# 411618_029_3_4.net
KiCad netlist of a schematic drawn in Altium Designer
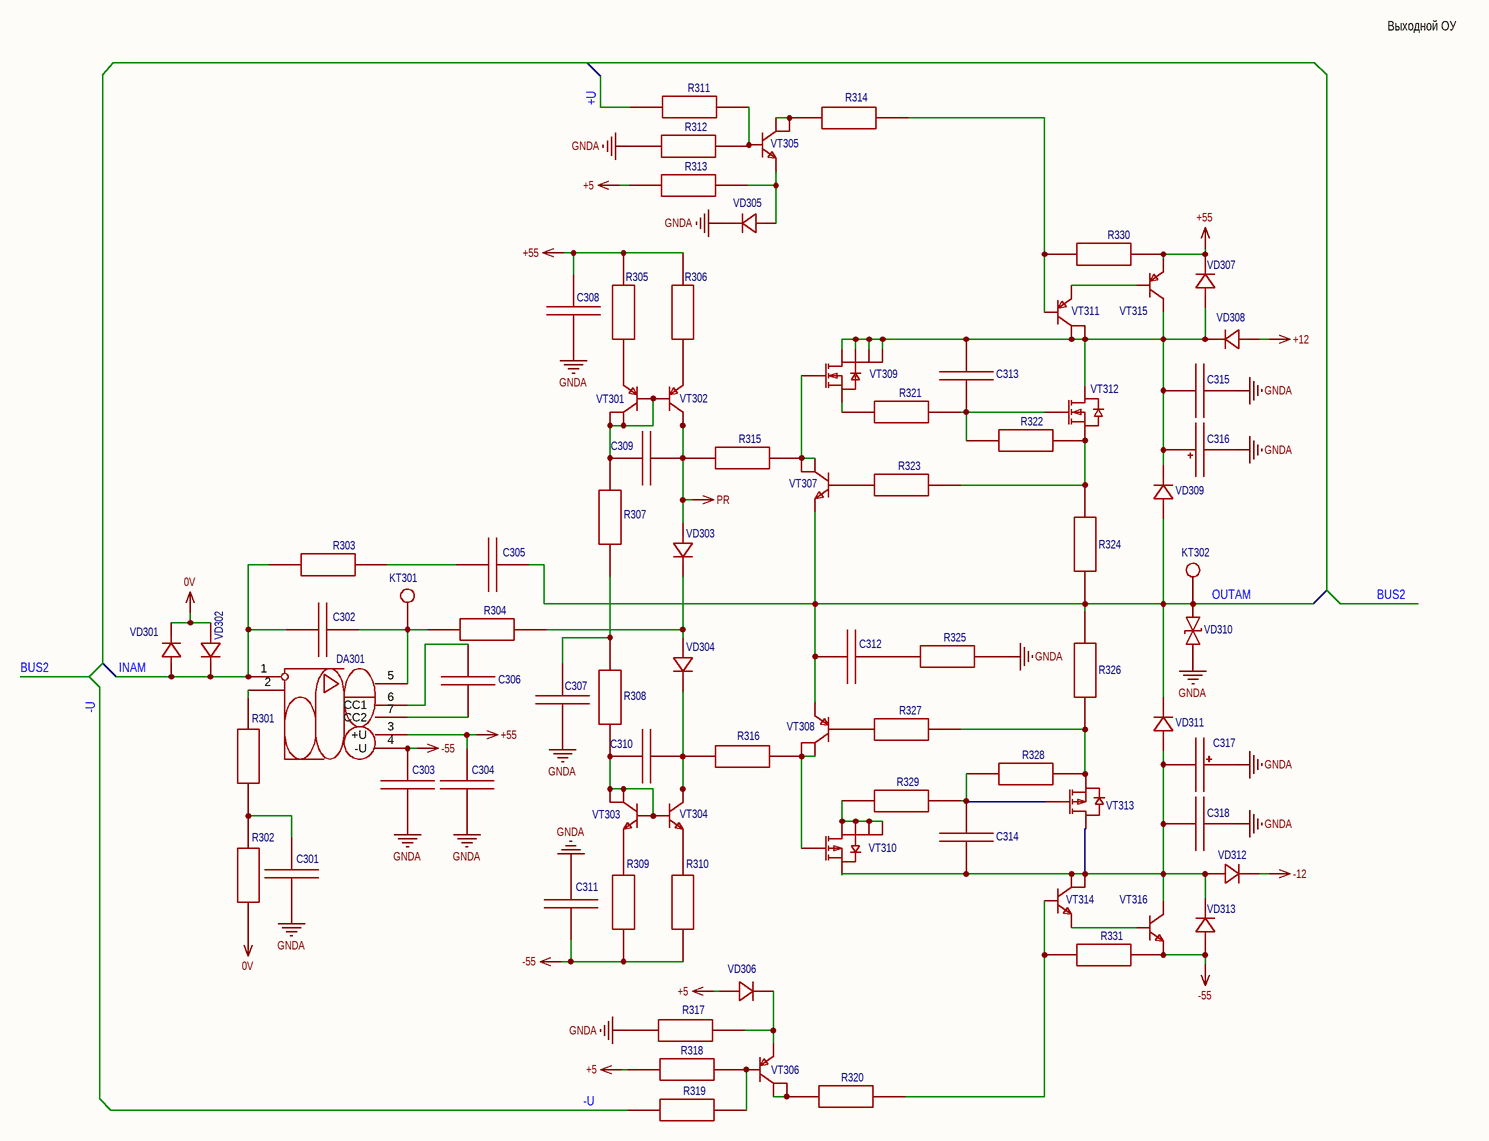
[diagram p0: УШЯИ.411618.029Э Э3 Лист 4.schdoc]

(export (version "E")
  (design (tool "Eeschema 10.0.6"))
  (components
    (comp (ref "C301")
      (value "Конденсатор SMD 1мкФ 100В X7R 10% [0805]")
      (footprint "C0805")
      (fields (field (name "MANUFACTURER PART") "C0805") (field (name "CONTRIBUTOR") "jordanjin"))
      (libsource (lib "altium-import") (part "root_1_Конденсатор SMD 1мкФ 100В X7R 10% [0805]_"))
    )
    (comp (ref "C302")
      (value "Конденсатор SMD 33пФ 100В X7R 10% [0805]")
      (footprint "C0805")
      (fields (field (name "MANUFACTURER PART") "C0805") (field (name "CONTRIBUTOR") "jordanjin"))
      (libsource (lib "altium-import") (part "root_2_Конденсатор SMD 33пФ 100В X7R 10% [0805]_"))
    )
    (comp (ref "C303")
      (value "Конденсатор SMD 68нФ 100В X7R 10% [0805]")
      (footprint "C0805")
      (fields (field (name "MANUFACTURER PART") "C0805") (field (name "CONTRIBUTOR") "jordanjin"))
      (libsource (lib "altium-import") (part "root_1_Конденсатор SMD 68нФ 100В X7R 10% [0805]_"))
    )
    (comp (ref "C304")
      (value "Конденсатор SMD 68нФ 100В X7R 10% [0805]")
      (footprint "C0805")
      (fields (field (name "MANUFACTURER PART") "C0805") (field (name "CONTRIBUTOR") "jordanjin"))
      (libsource (lib "altium-import") (part "root_1_Конденсатор SMD 68нФ 100В X7R 10% [0805]_"))
    )
    (comp (ref "C305")
      (value "Конденсатор SMD 10пФ 100В X7R 10% [0805]")
      (footprint "C0805")
      (fields (field (name "MANUFACTURER PART") "C0805") (field (name "CONTRIBUTOR") "jordanjin"))
      (libsource (lib "altium-import") (part "root_2_Конденсатор SMD 10пФ 100В X7R 10% [0805]_"))
    )
    (comp (ref "C306")
      (value "Конденсатор SMD 10пФ 100В X7R 10% [0805]")
      (footprint "C0805")
      (fields (field (name "MANUFACTURER PART") "C0805") (field (name "CONTRIBUTOR") "jordanjin"))
      (libsource (lib "altium-import") (part "root_3_Конденсатор SMD 10пФ 100В X7R 10% [0805]_"))
    )
    (comp (ref "C307")
      (value "Конденсатор SMD 68нФ 250В X7R 10% [0805]")
      (footprint "C0805")
      (fields (field (name "MANUFACTURER PART") "C0805") (field (name "CONTRIBUTOR") "jordanjin"))
      (libsource (lib "altium-import") (part "root_1_Конденсатор SMD 68нФ 250В X7R 10% [0805]_"))
    )
    (comp (ref "C308")
      (value "Конденсатор SMD 68нФ 250В X7R 10% [0805]")
      (footprint "C0805")
      (fields (field (name "MANUFACTURER PART") "C0805") (field (name "CONTRIBUTOR") "jordanjin"))
      (libsource (lib "altium-import") (part "root_3_Конденсатор SMD 68нФ 250В X7R 10% [0805]_"))
    )
    (comp (ref "C309")
      (value "Конденсатор SMD 10пФ 100В X7R 10% [0805]")
      (footprint "C0805")
      (fields (field (name "MANUFACTURER PART") "C0805") (field (name "CONTRIBUTOR") "jordanjin"))
      (libsource (lib "altium-import") (part "root_2_Конденсатор SMD 10пФ 100В X7R 10% [0805]_"))
    )
    (comp (ref "C310")
      (value "Конденсатор SMD 10пФ 100В X7R 10% [0805]")
      (footprint "C0805")
      (fields (field (name "MANUFACTURER PART") "C0805") (field (name "CONTRIBUTOR") "jordanjin"))
      (libsource (lib "") (part "root_2_Конденсатор SMD 10пФ 100В X7R 10% [0805]__1"))
    )
    (comp (ref "C311")
      (value "Конденсатор SMD 68нФ 250В X7R 10% [0805]")
      (footprint "C0805")
      (fields (field (name "MANUFACTURER PART") "C0805") (field (name "CONTRIBUTOR") "jordanjin"))
      (libsource (lib "altium-import") (part "root_3_Конденсатор SMD 68нФ 250В X7R 10% [0805]_"))
    )
    (comp (ref "C312")
      (value "Конденсатор SMD 10пФ 100В X7R 10% [0805]")
      (footprint "C0805")
      (fields (field (name "MANUFACTURER PART") "C0805") (field (name "CONTRIBUTOR") "jordanjin"))
      (libsource (lib "altium-import") (part "root_0_Конденсатор SMD 10пФ 100В X7R 10% [0805]_"))
    )
    (comp (ref "C313")
      (value "Конденсатор SMD 10пФ 100В X7R 10% [0805]")
      (footprint "C0805")
      (fields (field (name "MANUFACTURER PART") "C0805") (field (name "CONTRIBUTOR") "jordanjin"))
      (libsource (lib "altium-import") (part "root_3_Конденсатор SMD 10пФ 100В X7R 10% [0805]_"))
    )
    (comp (ref "C314")
      (value "Конденсатор SMD 10пФ 100В X7R 10% [0805]")
      (footprint "C0805")
      (fields (field (name "MANUFACTURER PART") "C0805") (field (name "CONTRIBUTOR") "jordanjin"))
      (libsource (lib "altium-import") (part "root_3_Конденсатор SMD 10пФ 100В X7R 10% [0805]_"))
    )
    (comp (ref "C315")
      (value "Конденсатор SMD 10пФ 100В X7R 10% [0805]")
      (footprint "C0805")
      (fields (field (name "MANUFACTURER PART") "C0805") (field (name "CONTRIBUTOR") "jordanjin"))
      (libsource (lib "altium-import") (part "root_0_Конденсатор SMD 10пФ 100В X7R 10% [0805]_"))
    )
    (comp (ref "C316")
      (value "ECAP (К50-35), 220мкФ, 100В, 105°C, 13x25, p:5мм")
      (footprint "CAP-TH_BD13.0-P5.00-D0.6-FD")
      (fields
        (field (name "MANUFACTURER") "JB Capacitors")
        (field (name "MANUFACTURER PART") "JRB2A221M05001300250000B")
        (field (name "CONTRIBUTOR") "jordanjin")
      )
      (libsource (lib "altium-import") (part "root_1_ECAP (К50-35), 220мкФ, 100В, 105°C, 13x25, p{colon}5мм_"))
    )
    (comp (ref "C317")
      (value "ECAP (К50-35), 220мкФ, 100В, 105°C, 13x25, p:5мм")
      (footprint "CAP-TH_BD13.0-P5.00-D0.6-FD")
      (fields
        (field (name "MANUFACTURER") "JB Capacitors")
        (field (name "MANUFACTURER PART") "JRB2A221M05001300250000B")
        (field (name "CONTRIBUTOR") "jordanjin")
      )
      (libsource (lib "altium-import") (part "root_3_ECAP (К50-35), 220мкФ, 100В, 105°C, 13x25, p{colon}5мм_"))
    )
    (comp (ref "C318")
      (value "Конденсатор SMD 10пФ 100В X7R 10% [0805]")
      (footprint "C0805")
      (fields (field (name "MANUFACTURER PART") "C0805") (field (name "CONTRIBUTOR") "jordanjin"))
      (libsource (lib "altium-import") (part "root_0_Конденсатор SMD 10пФ 100В X7R 10% [0805]_"))
    )
    (comp (ref "DA301")
      (value "Операционный усилитель PA340CC [TH]")
      (fields
        (field (name "MANUFACTURER") "Apex Microtechnology")
        (field (name "MANUFACTURER PART") "PA340CC")
        (field (name "CONTRIBUTOR") "jordanjin")
      )
      (libsource (lib "altium-import") (part "root_0_Операционный усилитель PA340CC [TH]_"))
    )
    (comp (ref "KT301")
      (value "Control point")
      (fields (field (name "CONTRIBUTOR") "jordanjin"))
      (libsource (lib "altium-import") (part "root_2_Control point_"))
    )
    (comp (ref "KT302")
      (value "Control point")
      (fields (field (name "CONTRIBUTOR") "jordanjin"))
      (libsource (lib "altium-import") (part "root_2_Control point_"))
    )
    (comp (ref "R301")
      (value "Резистор 4.6кОм 0,125Вт 1% [0805]")
      (footprint "R0805")
      (fields (field (name "MANUFACTURER PART") "R0805") (field (name "CONTRIBUTOR") "jordanjin"))
      (libsource (lib "altium-import") (part "root_1_Резистор 4.6кОм 0,125Вт 1% [0805]_"))
    )
    (comp (ref "R302")
      (value "Резистор 1.2кОм 0,125Вт 1% [0805]")
      (footprint "R0805")
      (fields (field (name "MANUFACTURER PART") "R0805") (field (name "CONTRIBUTOR") "jordanjin"))
      (libsource (lib "altium-import") (part "root_1_Резистор 1.2кОм 0,125Вт 1% [0805]_"))
    )
    (comp (ref "R303")
      (value "Резистор 1.8кОм 0,125Вт 1% [0805]")
      (footprint "R0805")
      (fields (field (name "MANUFACTURER PART") "R0805") (field (name "CONTRIBUTOR") "jordanjin"))
      (libsource (lib "altium-import") (part "root_2_Резистор 1.8кОм 0,125Вт 1% [0805]_"))
    )
    (comp (ref "R304")
      (value "Резистор 1.2кОм 0,125Вт 1% [0805]")
      (footprint "R0805")
      (fields (field (name "MANUFACTURER PART") "R0805") (field (name "CONTRIBUTOR") "jordanjin"))
      (libsource (lib "altium-import") (part "root_2_Резистор 1.2кОм 0,125Вт 1% [0805]_"))
    )
    (comp (ref "R305")
      (value "Резистор 220Ом 0,125Вт 1% [0805]")
      (footprint "R0805")
      (fields (field (name "MANUFACTURER PART") "R0805") (field (name "CONTRIBUTOR") "jordanjin"))
      (libsource (lib "") (part "root_3_Резистор 220Ом 0,125Вт 1% [0805]__1"))
    )
    (comp (ref "R306")
      (value "Резистор 220Ом 0,125Вт 1% [0805]")
      (footprint "R0805")
      (fields (field (name "MANUFACTURER PART") "R0805") (field (name "CONTRIBUTOR") "jordanjin"))
      (libsource (lib "") (part "root_3_Резистор 220Ом 0,125Вт 1% [0805]__1"))
    )
    (comp (ref "R307")
      (value "Резистор 22кОм 0,125Вт 1% [0805]")
      (footprint "R0805")
      (fields (field (name "MANUFACTURER PART") "R0805") (field (name "CONTRIBUTOR") "jordanjin"))
      (libsource (lib "altium-import") (part "root_3_Резистор 22кОм 0,125Вт 1% [0805]_"))
    )
    (comp (ref "R308")
      (value "Резистор 22кОм 0,125Вт 1% [0805]")
      (footprint "R0805")
      (fields (field (name "MANUFACTURER PART") "R0805") (field (name "CONTRIBUTOR") "jordanjin"))
      (libsource (lib "") (part "root_3_Резистор 22кОм 0,125Вт 1% [0805]__1"))
    )
    (comp (ref "R309")
      (value "Резистор 220Ом 0,125Вт 1% [0805]")
      (footprint "R0805")
      (fields (field (name "MANUFACTURER PART") "R0805") (field (name "CONTRIBUTOR") "jordanjin"))
      (libsource (lib "altium-import") (part "root_3_Резистор 220Ом 0,125Вт 1% [0805]_"))
    )
    (comp (ref "R310")
      (value "Резистор 220Ом 0,125Вт 1% [0805]")
      (footprint "R0805")
      (fields (field (name "MANUFACTURER PART") "R0805") (field (name "CONTRIBUTOR") "jordanjin"))
      (libsource (lib "altium-import") (part "root_3_Резистор 220Ом 0,125Вт 1% [0805]_"))
    )
    (comp (ref "R311")
      (value "Резистор 3кОм 0,125Вт 1% [0805]")
      (footprint "R0805")
      (fields (field (name "MANUFACTURER PART") "R0805") (field (name "CONTRIBUTOR") "jordanjin"))
      (libsource (lib "") (part "root_0_Резистор 3кОм 0,125Вт 1% [0805]__1"))
    )
    (comp (ref "R312")
      (value "Резистор 2.4кОм 0,125Вт 1% [0805]")
      (footprint "R0805")
      (fields (field (name "MANUFACTURER PART") "R0805") (field (name "CONTRIBUTOR") "jordanjin"))
      (libsource (lib "") (part "root_0_Резистор 2.4кОм 0,125Вт 1% [0805]__1"))
    )
    (comp (ref "R313")
      (value "Резистор 7.2кОм 0,125Вт 1% [0805]")
      (footprint "R0805")
      (fields (field (name "MANUFACTURER PART") "R0805") (field (name "CONTRIBUTOR") "jordanjin"))
      (libsource (lib "") (part "root_0_Резистор 7.2кОм 0,125Вт 1% [0805]__1"))
    )
    (comp (ref "R314")
      (value "Резистор 18кОм 0,125Вт 1% [0805]")
      (footprint "R0805")
      (fields (field (name "MANUFACTURER PART") "R0805") (field (name "CONTRIBUTOR") "jordanjin"))
      (libsource (lib "altium-import") (part "root_0_Резистор 18кОм 0,125Вт 1% [0805]_"))
    )
    (comp (ref "R315")
      (value "Резистор 120Ом 0,125Вт 1% [0805]")
      (footprint "R0805")
      (fields (field (name "MANUFACTURER PART") "R0805") (field (name "CONTRIBUTOR") "jordanjin"))
      (libsource (lib "altium-import") (part "root_0_Резистор 120Ом 0,125Вт 1% [0805]_"))
    )
    (comp (ref "R316")
      (value "Резистор 120Ом 0,125Вт 1% [0805]")
      (footprint "R0805")
      (fields (field (name "MANUFACTURER PART") "R0805") (field (name "CONTRIBUTOR") "jordanjin"))
      (libsource (lib "altium-import") (part "root_0_Резистор 120Ом 0,125Вт 1% [0805]_"))
    )
    (comp (ref "R317")
      (value "Резистор 7.2кОм 0,125Вт 1% [0805]")
      (footprint "R0805")
      (fields (field (name "MANUFACTURER PART") "R0805") (field (name "CONTRIBUTOR") "jordanjin"))
      (libsource (lib "altium-import") (part "root_0_Резистор 7.2кОм 0,125Вт 1% [0805]_"))
    )
    (comp (ref "R318")
      (value "Резистор 2.4кОм 0,125Вт 1% [0805]")
      (footprint "R0805")
      (fields (field (name "MANUFACTURER PART") "R0805") (field (name "CONTRIBUTOR") "jordanjin"))
      (libsource (lib "altium-import") (part "root_0_Резистор 2.4кОм 0,125Вт 1% [0805]_"))
    )
    (comp (ref "R319")
      (value "Резистор 3кОм 0,125Вт 1% [0805]")
      (footprint "R0805")
      (fields (field (name "MANUFACTURER PART") "R0805") (field (name "CONTRIBUTOR") "jordanjin"))
      (libsource (lib "altium-import") (part "root_0_Резистор 3кОм 0,125Вт 1% [0805]_"))
    )
    (comp (ref "R320")
      (value "Резистор 18кОм 0,125Вт 1% [0805]")
      (footprint "R0805")
      (fields (field (name "MANUFACTURER PART") "R0805") (field (name "CONTRIBUTOR") "jordanjin"))
      (libsource (lib "") (part "root_0_Резистор 18кОм 0,125Вт 1% [0805]__1"))
    )
    (comp (ref "R321")
      (value "Резистор 240Ом 0.25Вт 1% [1206]")
      (footprint "R0805")
      (fields (field (name "MANUFACTURER PART") "R0805") (field (name "CONTRIBUTOR") "jordanjin"))
      (libsource (lib "") (part "root_0_Резистор 240Ом 0.25Вт 1% [1206]__1"))
    )
    (comp (ref "R322")
      (value "Резистор 1кОм 0,125Вт 5% [0805]")
      (footprint "R0805")
      (fields (field (name "MANUFACTURER PART") "R0805") (field (name "CONTRIBUTOR") "jordanjin"))
      (libsource (lib "altium-import") (part "root_2_Резистор 1кОм 0,125Вт 5% [0805]_"))
    )
    (comp (ref "R323")
      (value "Резистор 300Ом 0,125Вт 1% [0805]")
      (footprint "R0805")
      (fields (field (name "MANUFACTURER PART") "R0805") (field (name "CONTRIBUTOR") "jordanjin"))
      (libsource (lib "") (part "root_0_Резистор 300Ом 0,125Вт 1% [0805]__1"))
    )
    (comp (ref "R324")
      (value "Резистор MP930-0.04-1% [TO-220-2]")
      (footprint "TO-220-2_L10.4-W3.2-P5.08-L")
      (fields (field (name "MANUFACTURER PART") "MP930-0.04-1%") (field (name "CONTRIBUTOR") "jordanjin"))
      (libsource (lib "altium-import") (part "root_1_Резистор MP930-0.04-1% [TO-220-2]_"))
    )
    (comp (ref "R325")
      (value "Резистор 100Ом 0,125Вт 1% [0805]")
      (footprint "R0805")
      (fields (field (name "MANUFACTURER PART") "R0805") (field (name "CONTRIBUTOR") "jordanjin"))
      (libsource (lib "altium-import") (part "root_0_Резистор 100Ом 0,125Вт 1% [0805]_"))
    )
    (comp (ref "R326")
      (value "Резистор MP930-0.04-1% [TO-220-2]")
      (footprint "TO-220-2_L10.4-W3.2-P5.08-L")
      (fields (field (name "MANUFACTURER PART") "MP930-0.04-1%") (field (name "CONTRIBUTOR") "jordanjin"))
      (libsource (lib "") (part "root_1_Резистор MP930-0.04-1% [TO-220-2]__1"))
    )
    (comp (ref "R327")
      (value "Резистор 300Ом 0,125Вт 1% [0805]")
      (footprint "R0805")
      (fields (field (name "MANUFACTURER PART") "R0805") (field (name "CONTRIBUTOR") "jordanjin"))
      (libsource (lib "altium-import") (part "root_0_Резистор 300Ом 0,125Вт 1% [0805]_"))
    )
    (comp (ref "R328")
      (value "Резистор 1кОм 0,125Вт 5% [0805]")
      (footprint "R0805")
      (fields (field (name "MANUFACTURER PART") "R0805") (field (name "CONTRIBUTOR") "jordanjin"))
      (libsource (lib "altium-import") (part "root_0_Резистор 1кОм 0,125Вт 5% [0805]_"))
    )
    (comp (ref "R329")
      (value "Резистор 240Ом 0.25Вт 1% [1206]")
      (footprint "R0805")
      (fields (field (name "MANUFACTURER PART") "R0805") (field (name "CONTRIBUTOR") "jordanjin"))
      (libsource (lib "altium-import") (part "root_0_Резистор 240Ом 0.25Вт 1% [1206]_"))
    )
    (comp (ref "R330")
      (value "Резистор 1.5кОм 0,125Вт 1% [0805]")
      (footprint "R0805")
      (fields (field (name "MANUFACTURER PART") "R0805") (field (name "CONTRIBUTOR") "jordanjin"))
      (libsource (lib "altium-import") (part "root_0_Резистор 1.5кОм 0,125Вт 1% [0805]_"))
    )
    (comp (ref "R331")
      (value "Резистор 1.5кОм 0,125Вт 1% [0805]")
      (footprint "R0805")
      (fields (field (name "MANUFACTURER PART") "R0805") (field (name "CONTRIBUTOR") "jordanjin"))
      (libsource (lib "altium-import") (part "root_0_Резистор 1.5кОм 0,125Вт 1% [0805]_"))
    )
    (comp (ref "VD301")
      (value "Диод импульсный 1N4448 [SOD-123]")
      (footprint "SOD-123_L2.7-W1.6-LS3.7-RD-1")
      (fields
        (field (name "MANUFACTURER") "YANGJIE")
        (field (name "MANUFACTURER PART") "1N4448WQ")
        (field (name "CONTRIBUTOR") "jordanjin")
      )
      (libsource (lib "altium-import") (part "root_3_Диод импульсный 1N4448 [SOD-123]_"))
    )
    (comp (ref "VD302")
      (value "Диод импульсный 1N4448 [SOD-123]")
      (footprint "SOD-123_L2.7-W1.6-LS3.7-RD-1")
      (fields
        (field (name "MANUFACTURER") "YANGJIE")
        (field (name "MANUFACTURER PART") "1N4448WQ")
        (field (name "CONTRIBUTOR") "jordanjin")
      )
      (libsource (lib "altium-import") (part "root_1_Диод импульсный 1N4448 [SOD-123]_"))
    )
    (comp (ref "VD303")
      (value "Диод импульсный 1N4448 [SOD-123]")
      (footprint "SOD-123_L2.7-W1.6-LS3.7-RD-1")
      (fields
        (field (name "MANUFACTURER") "YANGJIE")
        (field (name "MANUFACTURER PART") "1N4448WQ")
        (field (name "CONTRIBUTOR") "jordanjin")
      )
      (libsource (lib "altium-import") (part "root_1_Диод импульсный 1N4448 [SOD-123]_"))
    )
    (comp (ref "VD304")
      (value "Диод импульсный 1N4448 [SOD-123]")
      (footprint "SOD-123_L2.7-W1.6-LS3.7-RD-1")
      (fields
        (field (name "MANUFACTURER") "YANGJIE")
        (field (name "MANUFACTURER PART") "1N4448WQ")
        (field (name "CONTRIBUTOR") "jordanjin")
      )
      (libsource (lib "") (part "root_3_Диод импульсный 1N4448 [SOD-123]__1"))
    )
    (comp (ref "VD305")
      (value "Диод импульсный 1N4448 [SOD-123]")
      (footprint "SOD-123_L2.7-W1.6-LS3.7-RD-1")
      (fields
        (field (name "MANUFACTURER") "YANGJIE")
        (field (name "MANUFACTURER PART") "1N4448WQ")
        (field (name "CONTRIBUTOR") "jordanjin")
      )
      (libsource (lib "altium-import") (part "root_0_Диод импульсный 1N4448 [SOD-123]_"))
    )
    (comp (ref "VD306")
      (value "Диод импульсный 1N4448 [SOD-123]")
      (footprint "SOD-123_L2.7-W1.6-LS3.7-RD-1")
      (fields
        (field (name "MANUFACTURER") "YANGJIE")
        (field (name "MANUFACTURER PART") "1N4448WQ")
        (field (name "CONTRIBUTOR") "jordanjin")
      )
      (libsource (lib "altium-import") (part "root_2_Диод импульсный 1N4448 [SOD-123]_"))
    )
    (comp (ref "VD307")
      (value "Диод RS1M [SMA] (допускается замена на FR307 [DO-201AD])")
      (fields
        (field (name "MANUFACTURER") "Wild Goose(威谷)")
        (field (name "MANUFACTURER PART") "RS1M")
        (field (name "CONTRIBUTOR") "lcsc")
      )
      (libsource (lib "altium-import") (part "root_3_Диод RS1M [SMA] (допускается замена на FR307 [DO-201AD])_"))
    )
    (comp (ref "VD308")
      (value "Диод КД2970А [TO-220AC]")
      (footprint "TO-220AC-2_L10.0-W4.5-P5.08-T")
      (fields
        (field (name "MANUFACTURER") "NH(纽航)")
        (field (name "MANUFACTURER PART") "MUR1560F")
        (field (name "CONTRIBUTOR") "lcsc")
      )
      (libsource (lib "altium-import") (part "root_0_Диод КД2970А [TO-220AC]_"))
    )
    (comp (ref "VD309")
      (value "Диод RS1M [SMA] (допускается замена на FR307 [DO-201AD])")
      (fields
        (field (name "MANUFACTURER") "Wild Goose(威谷)")
        (field (name "MANUFACTURER PART") "RS1M")
        (field (name "CONTRIBUTOR") "lcsc")
      )
      (libsource (lib "altium-import") (part "root_3_Диод RS1M [SMA] (допускается замена на FR307 [DO-201AD])_"))
    )
    (comp (ref "VD310")
      (value "Диод защитный 1.5KE56CA [DO-201AD/DO-27]")
      (footprint "DO-201")
      (fields
        (field (name "MANUFACTURER") "Littelfuse(美国力特)")
        (field (name "MANUFACTURER PART") "1.5KE56CA")
        (field (name "CONTRIBUTOR") "LCSC")
      )
      (libsource (lib "altium-import") (part "root_1_Диод защитный 1.5KE56CA [DO-201AD/DO-27]_"))
    )
    (comp (ref "VD311")
      (value "Диод RS1M [SMA] (допускается замена на FR307 [DO-201AD])")
      (fields
        (field (name "MANUFACTURER") "Wild Goose(威谷)")
        (field (name "MANUFACTURER PART") "RS1M")
        (field (name "CONTRIBUTOR") "lcsc")
      )
      (libsource (lib "altium-import") (part "root_3_Диод RS1M [SMA] (допускается замена на FR307 [DO-201AD])_"))
    )
    (comp (ref "VD312")
      (value "Диод КД2970А [TO-220AC]")
      (footprint "TO-220AC-2_L10.0-W4.5-P5.08-T")
      (fields
        (field (name "MANUFACTURER") "NH(纽航)")
        (field (name "MANUFACTURER PART") "MUR1560F")
        (field (name "CONTRIBUTOR") "lcsc")
      )
      (libsource (lib "altium-import") (part "root_2_Диод КД2970А [TO-220AC]_"))
    )
    (comp (ref "VD313")
      (value "Диод RS1M [SMA] (допускается замена на FR307 [DO-201AD])")
      (fields
        (field (name "MANUFACTURER") "Wild Goose(威谷)")
        (field (name "MANUFACTURER PART") "RS1M")
        (field (name "CONTRIBUTOR") "lcsc")
      )
      (libsource (lib "altium-import") (part "root_3_Диод RS1M [SMA] (допускается замена на FR307 [DO-201AD])_"))
    )
    (comp (ref "VT301")
      (value "Транзистор DZTA92 PNP [SOT223]")
      (footprint "SOT-223-3_L6.5-W3.4-P2.30-LS7.0-BR")
      (fields
        (field (name "MANUFACTURER") "DIODES(美台)")
        (field (name "MANUFACTURER PART") "DZTA92-13")
        (field (name "CONTRIBUTOR") "lcsc")
      )
      (libsource (lib "altium-import") (part "root_0_Транзистор DZTA92 PNP [SOT223]_"))
    )
    (comp (ref "VT302")
      (value "Транзистор FZT758 PNP [SOT223]")
      (footprint "SOT-223_L6.5-W3.5-P2.30-LS7.0-BR")
      (fields
        (field (name "MANUFACTURER") "DIODES(美台)")
        (field (name "MANUFACTURER PART") "FZT758TA")
        (field (name "CONTRIBUTOR") "LCSC")
      )
      (libsource (lib "altium-import") (part "root_0_Транзистор FZT758 PNP [SOT223]_"))
    )
    (comp (ref "VT303")
      (value "Транзистор DZTA42 NPN [SOT223]")
      (footprint "SOT-223-4_L6.5-W3.5-P2.30-LS7.0-BR")
      (fields
        (field (name "MANUFACTURER") "DIODES(美台)")
        (field (name "MANUFACTURER PART") "DZTA42-13")
        (field (name "CONTRIBUTOR") "LCSC")
      )
      (libsource (lib "") (part "root_0_Транзистор DZTA42 NPN [SOT223]__1"))
    )
    (comp (ref "VT304")
      (value "Транзистор FZT658 NPN [SOT223]")
      (footprint "SOT-223_L6.5-W3.5-P2.30-LS7.0-BR")
      (fields
        (field (name "MANUFACTURER") "DIODES(美台)")
        (field (name "MANUFACTURER PART") "FZT658")
        (field (name "CONTRIBUTOR") "lcsc")
      )
      (libsource (lib "altium-import") (part "root_0_Транзистор FZT658 NPN [SOT223]_"))
    )
    (comp (ref "VT305")
      (value "Транзистор DZTA42 NPN [SOT223]")
      (footprint "SOT-223-4_L6.5-W3.5-P2.30-LS7.0-BR")
      (fields
        (field (name "MANUFACTURER") "DIODES(美台)")
        (field (name "MANUFACTURER PART") "DZTA42-13")
        (field (name "CONTRIBUTOR") "LCSC")
      )
      (libsource (lib "altium-import") (part "root_0_Транзистор DZTA42 NPN [SOT223]_"))
    )
    (comp (ref "VT306")
      (value "Транзистор DZTA92 PNP [SOT223]")
      (footprint "SOT-223-3_L6.5-W3.4-P2.30-LS7.0-BR")
      (fields
        (field (name "MANUFACTURER") "DIODES(美台)")
        (field (name "MANUFACTURER PART") "DZTA92-13")
        (field (name "CONTRIBUTOR") "lcsc")
      )
      (libsource (lib "") (part "root_0_Транзистор DZTA92 PNP [SOT223]__1"))
    )
    (comp (ref "VT307")
      (value "Транзистор DZTA42 NPN [SOT223]")
      (footprint "SOT-223-4_L6.5-W3.5-P2.30-LS7.0-BR")
      (fields
        (field (name "MANUFACTURER") "DIODES(美台)")
        (field (name "MANUFACTURER PART") "DZTA42-13")
        (field (name "CONTRIBUTOR") "LCSC")
      )
      (libsource (lib "") (part "root_0_Транзистор DZTA42 NPN [SOT223]__1"))
    )
    (comp (ref "VT308")
      (value "Транзистор DZTA92 PNP [SOT223]")
      (footprint "SOT-223-3_L6.5-W3.4-P2.30-LS7.0-BR")
      (fields
        (field (name "MANUFACTURER") "DIODES(美台)")
        (field (name "MANUFACTURER PART") "DZTA92-13")
        (field (name "CONTRIBUTOR") "lcsc")
      )
      (libsource (lib "altium-import") (part "root_0_Транзистор DZTA92 PNP [SOT223]_"))
    )
    (comp (ref "VT309")
      (value "Транзистор ZXMN10A08E6 N-канал 100В 1.9А [SOT-23-6]")
      (footprint "SOT-23-6_L2.9-W1.6-P0.95-LS2.7-BL")
      (fields
        (field (name "MANUFACTURER") "VBsemi(微碧半导体)")
        (field (name "MANUFACTURER PART") "ZXMN10A08E6TA-VB")
        (field (name "CONTRIBUTOR") "lcsc")
      )
      (libsource (lib "altium-import") (part "root_0_Транзистор ZXMN10A08E6 N-канал 100В 1.9А [SOT-23-6]_"))
    )
    (comp (ref "VT310")
      (value "Транзистор ZXMP10A17E6 P-канал 100В 1.3А [SOT-23-6]")
      (footprint "SOT-23-6_L2.9-W1.6-P0.95-LS2.8-BL")
      (fields
        (field (name "MANUFACTURER") "DIODES(美台)")
        (field (name "MANUFACTURER PART") "ZXMP10A17E6QTA")
        (field (name "CONTRIBUTOR") "lcsc")
      )
      (libsource (lib "altium-import") (part "root_0_Транзистор ZXMP10A17E6 P-канал 100В 1.3А [SOT-23-6]_"))
    )
    (comp (ref "VT311")
      (value "Транзистор DZTA92 PNP [SOT223]")
      (footprint "SOT-223-3_L6.5-W3.4-P2.30-LS7.0-BR")
      (fields
        (field (name "MANUFACTURER") "DIODES(美台)")
        (field (name "MANUFACTURER PART") "DZTA92-13")
        (field (name "CONTRIBUTOR") "lcsc")
      )
      (libsource (lib "") (part "root_0_Транзистор DZTA92 PNP [SOT223]__1"))
    )
    (comp (ref "VT312")
      (value "Транзистор FQP13N10  N-канал 100В 12.8А [TO-220]")
      (fields
        (field (name "MANUFACTURER") "onsemi(安森美)")
        (field (name "MANUFACTURER PART") "FQP13N10")
        (field (name "CONTRIBUTOR") "lcsc")
      )
      (libsource (lib "altium-import") (part "root_0_Транзистор FQP13N10  N-канал 100В 12.8А [TO-220]_"))
    )
    (comp (ref "VT313")
      (value "Транзистор SFP9530 P-канал 100В 10.5А [TO-220]")
      (fields
        (field (name "MANUFACTURER") "onsemi")
        (field (name "MANUFACTURER PART") "SFP9530")
        (field (name "CONTRIBUTOR") "jordanjin")
      )
      (libsource (lib "altium-import") (part "root_2_mirrored_Транзистор SFP9530 P-канал 100В 10.5А [TO-220]_"))
    )
    (comp (ref "VT314")
      (value "Транзистор DZTA42 NPN [SOT223]")
      (footprint "SOT-223-4_L6.5-W3.5-P2.30-LS7.0-BR")
      (fields
        (field (name "MANUFACTURER") "DIODES(美台)")
        (field (name "MANUFACTURER PART") "DZTA42-13")
        (field (name "CONTRIBUTOR") "LCSC")
      )
      (libsource (lib "altium-import") (part "root_0_Транзистор DZTA42 NPN [SOT223]_"))
    )
    (comp (ref "VT315")
      (value "Транзистор MJE5730G PNP [TO-220-3]")
      (footprint "TO-220-3_L10.0-W4.5-P2.54-L")
      (fields
        (field (name "MANUFACTURER") "onsemi(安森美)")
        (field (name "MANUFACTURER PART") "MJE5730G")
        (field (name "CONTRIBUTOR") "LCSC")
      )
      (libsource (lib "altium-import") (part "root_0_Транзистор MJE5730G PNP [TO-220-3]_"))
    )
    (comp (ref "VT316")
      (value "Транзистор TIP48 NPN [TO-220-3]")
      (footprint "TO-220-3_L10.0-W4.5-P2.54-L")
      (fields
        (field (name "MANUFACTURER") "onsemi(安森美)")
        (field (name "MANUFACTURER PART") "TIP48G")
        (field (name "CONTRIBUTOR") "lcsc")
      )
      (libsource (lib "altium-import") (part "root_0_Транзистор TIP48 NPN [TO-220-3]_"))
    )
  )
  (nets
    (net (code "2") (name "+5") (class "Default")
      (node (ref "R313") (pin "1") (pinfunction "1_1") (pintype "passive"))
      (node (ref "R318") (pin "1") (pinfunction "1_1") (pintype "passive"))
      (node (ref "VD306") (pin "2") (pinfunction "A_2") (pintype "passive"))
    )
    (net (code "3") (name "+12") (class "Default")
      (node (ref "VD308") (pin "3") (pinfunction "A_3") (pintype "passive"))
    )
    (net (code "4") (name "+55") (class "Default")
      (node (ref "C304") (pin "2") (pinfunction "2_2") (pintype "passive"))
      (node (ref "C308") (pin "1") (pinfunction "1_1") (pintype "passive"))
      (node (ref "DA301") (pin "3") (pinfunction "+U_3") (pintype "passive"))
      (node (ref "R305") (pin "1") (pinfunction "1_1") (pintype "passive"))
      (node (ref "R306") (pin "1") (pinfunction "1_1") (pintype "passive"))
      (node (ref "R330") (pin "2") (pinfunction "2_2") (pintype "passive"))
      (node (ref "VD307") (pin "1") (pinfunction "K_1") (pintype "passive"))
      (node (ref "VT315") (pin "3") (pinfunction "E_3") (pintype "passive"))
    )
    (net (code "5") (name "-12") (class "Default")
      (node (ref "VD312") (pin "1") (pinfunction "K_1") (pintype "passive"))
    )
    (net (code "6") (name "-55") (class "Default")
      (node (ref "C303") (pin "2") (pinfunction "2_2") (pintype "passive"))
      (node (ref "C311") (pin "2") (pinfunction "2_2") (pintype "passive"))
      (node (ref "DA301") (pin "4") (pinfunction "-U_4") (pintype "passive"))
      (node (ref "R309") (pin "1") (pinfunction "1_1") (pintype "passive"))
      (node (ref "R310") (pin "1") (pinfunction "1_1") (pintype "passive"))
      (node (ref "R331") (pin "2") (pinfunction "2_2") (pintype "passive"))
      (node (ref "VD313") (pin "2") (pinfunction "A_2") (pintype "passive"))
      (node (ref "VT316") (pin "3") (pinfunction "E_3") (pintype "passive"))
    )
    (net (code "7") (name "/+U") (class "Default")
      (node (ref "R311") (pin "1") (pinfunction "1_1") (pintype "passive"))
    )
    (net (code "8") (name "/-U") (class "Default")
      (node (ref "R319") (pin "1") (pinfunction "1_1") (pintype "passive"))
    )
    (net (code "9") (name "/INAM") (class "Default")
      (node (ref "C302") (pin "2") (pinfunction "2_2") (pintype "passive"))
      (node (ref "DA301") (pin "1") (pinfunction "-_1") (pintype "passive"))
      (node (ref "R303") (pin "2") (pinfunction "2_2") (pintype "passive"))
      (node (ref "VD301") (pin "2") (pinfunction "A_2") (pintype "passive"))
      (node (ref "VD302") (pin "1") (pinfunction "C_1") (pintype "passive"))
    )
    (net (code "10") (name "/OUTAM") (class "Default")
      (node (ref "C305") (pin "1") (pinfunction "1_1") (pintype "passive"))
      (node (ref "C312") (pin "1") (pinfunction "1_1") (pintype "passive"))
      (node (ref "KT302") (pin "1") (pinfunction "1_1") (pintype "passive"))
      (node (ref "R324") (pin "1") (pinfunction "1_1") (pintype "passive"))
      (node (ref "R326") (pin "2") (pinfunction "2_2") (pintype "passive"))
      (node (ref "VD309") (pin "2") (pinfunction "A_2") (pintype "passive"))
      (node (ref "VD310") (pin "2") (pinfunction "2_2") (pintype "passive"))
      (node (ref "VD311") (pin "1") (pinfunction "K_1") (pintype "passive"))
      (node (ref "VT307") (pin "3") (pinfunction "E_3") (pintype "passive"))
      (node (ref "VT308") (pin "3") (pinfunction "E_3") (pintype "passive"))
    )
    (net (code "12") (name "0V") (class "Default")
      (node (ref "R302") (pin "1") (pinfunction "1_1") (pintype "passive"))
      (node (ref "VD301") (pin "1") (pinfunction "C_1") (pintype "passive"))
      (node (ref "VD302") (pin "2") (pinfunction "A_2") (pintype "passive"))
    )
    (net (code "13") (name "GNDA") (class "Default")
      (node (ref "C301") (pin "1") (pinfunction "1_1") (pintype "passive"))
      (node (ref "C303") (pin "1") (pinfunction "1_1") (pintype "passive"))
      (node (ref "C304") (pin "1") (pinfunction "1_1") (pintype "passive"))
      (node (ref "C307") (pin "1") (pinfunction "1_1") (pintype "passive"))
      (node (ref "C308") (pin "2") (pinfunction "2_2") (pintype "passive"))
      (node (ref "C311") (pin "1") (pinfunction "1_1") (pintype "passive"))
      (node (ref "C315") (pin "2") (pinfunction "2_2") (pintype "passive"))
      (node (ref "C316") (pin "2") (pinfunction "2_2") (pintype "passive"))
      (node (ref "C317") (pin "1") (pinfunction "1_1") (pintype "passive"))
      (node (ref "C318") (pin "2") (pinfunction "2_2") (pintype "passive"))
      (node (ref "R312") (pin "1") (pinfunction "1_1") (pintype "passive"))
      (node (ref "R317") (pin "1") (pinfunction "1_1") (pintype "passive"))
      (node (ref "R325") (pin "2") (pinfunction "2_2") (pintype "passive"))
      (node (ref "VD305") (pin "1") (pinfunction "C_1") (pintype "passive"))
      (node (ref "VD310") (pin "1") (pinfunction "1_1") (pintype "passive"))
    )
    (net (code "14") (name "Net-(C301-Pad2)") (class "Default")
      (node (ref "C301") (pin "2") (pinfunction "2_2") (pintype "passive"))
      (node (ref "R301") (pin "1") (pinfunction "1_1") (pintype "passive"))
      (node (ref "R302") (pin "2") (pinfunction "2_2") (pintype "passive"))
    )
    (net (code "15") (name "Net-(C305-Pad2)") (class "Default")
      (node (ref "C305") (pin "2") (pinfunction "2_2") (pintype "passive"))
      (node (ref "R303") (pin "1") (pinfunction "1_1") (pintype "passive"))
    )
    (net (code "16") (name "Net-(C307-Pad2)") (class "Default")
      (node (ref "C307") (pin "2") (pinfunction "2_2") (pintype "passive"))
      (node (ref "R307") (pin "2") (pinfunction "2_2") (pintype "passive"))
      (node (ref "R308") (pin "2") (pinfunction "2_2") (pintype "passive"))
    )
    (net (code "17") (name "Net-(C312-Pad2)") (class "Default")
      (node (ref "C312") (pin "2") (pinfunction "2_2") (pintype "passive"))
      (node (ref "R325") (pin "1") (pinfunction "1_1") (pintype "passive"))
    )
    (net (code "18") (name "Net-(DA301-+)") (class "Default")
      (node (ref "DA301") (pin "2") (pinfunction "+_2") (pintype "passive"))
      (node (ref "R301") (pin "2") (pinfunction "2_2") (pintype "passive"))
    )
    (net (code "19") (name "Net-(DA301-CC1)") (class "Default")
      (node (ref "C306") (pin "1") (pinfunction "1_1") (pintype "passive"))
      (node (ref "DA301") (pin "6") (pinfunction "CC1_6") (pintype "passive"))
    )
    (net (code "20") (name "Net-(DA301-CC2)") (class "Default")
      (node (ref "C306") (pin "2") (pinfunction "2_2") (pintype "passive"))
      (node (ref "DA301") (pin "7") (pinfunction "CC2_7") (pintype "passive"))
    )
    (net (code "21") (name "Net-(DA301-Out)") (class "Default")
      (node (ref "C302") (pin "1") (pinfunction "1_1") (pintype "passive"))
      (node (ref "DA301") (pin "5") (pinfunction "Out_5") (pintype "passive"))
      (node (ref "KT301") (pin "1") (pinfunction "1_1") (pintype "passive"))
      (node (ref "R304") (pin "2") (pinfunction "2_2") (pintype "passive"))
    )
    (net (code "22") (name "Net-(R314-Pad1)") (class "Default")
      (node (ref "R314") (pin "1") (pinfunction "1_1") (pintype "passive"))
      (node (ref "VT305") (pin "2") (pinfunction "C_2") (pintype "passive"))
      (node (ref "VT305") (pin "4") (pinfunction "C_4") (pintype "passive"))
    )
    (net (code "23") (name "Net-(R320-Pad1)") (class "Default")
      (node (ref "R320") (pin "1") (pinfunction "1_1") (pintype "passive"))
      (node (ref "VT306") (pin "2") (pinfunction "C_2") (pintype "passive"))
      (node (ref "VT306") (pin "4") (pinfunction "C_4") (pintype "passive"))
    )
    (net (code "24") (name "Net-(R329-Pad1)") (class "Default")
      (node (ref "R329") (pin "1") (pinfunction "1_1") (pintype "passive"))
      (node (ref "VT310") (pin "1") (pinfunction "D_1") (pintype "passive"))
      (node (ref "VT310") (pin "2") (pinfunction "D_2") (pintype "passive"))
      (node (ref "VT310") (pin "5") (pinfunction "D_5") (pintype "passive"))
      (node (ref "VT310") (pin "6") (pinfunction "D_6") (pintype "passive"))
    )
    (net (code "25") (name "Net-(VD303-C)") (class "Default")
      (node (ref "R304") (pin "1") (pinfunction "1_1") (pintype "passive"))
      (node (ref "VD303") (pin "1") (pinfunction "C_1") (pintype "passive"))
      (node (ref "VD304") (pin "2") (pinfunction "A_2") (pintype "passive"))
    )
    (net (code "26") (name "Net-(VD304-C)") (class "Default")
      (node (ref "C310") (pin "1") (pinfunction "1_1") (pintype "passive"))
      (node (ref "R316") (pin "1") (pinfunction "1_1") (pintype "passive"))
      (node (ref "VD304") (pin "1") (pinfunction "C_1") (pintype "passive"))
      (node (ref "VT304") (pin "2") (pinfunction "C_2") (pintype "passive"))
      (node (ref "VT304") (pin "4") (pinfunction "C_4") (pintype "passive"))
    )
    (net (code "27") (name "Net-(VD305-A)") (class "Default")
      (node (ref "R313") (pin "2") (pinfunction "2_2") (pintype "passive"))
      (node (ref "VD305") (pin "2") (pinfunction "A_2") (pintype "passive"))
      (node (ref "VT305") (pin "3") (pinfunction "E_3") (pintype "passive"))
    )
    (net (code "28") (name "Net-(VD306-C)") (class "Default")
      (node (ref "R317") (pin "2") (pinfunction "2_2") (pintype "passive"))
      (node (ref "VD306") (pin "1") (pinfunction "C_1") (pintype "passive"))
      (node (ref "VT306") (pin "3") (pinfunction "E_3") (pintype "passive"))
    )
    (net (code "29") (name "Net-(VD307-A)") (class "Default")
      (node (ref "C313") (pin "1") (pinfunction "1_1") (pintype "passive"))
      (node (ref "C315") (pin "1") (pinfunction "1_1") (pintype "passive"))
      (node (ref "C316") (pin "1") (pinfunction "1_1") (pintype "passive"))
      (node (ref "VD307") (pin "2") (pinfunction "A_2") (pintype "passive"))
      (node (ref "VD308") (pin "1") (pinfunction "K_1") (pintype "passive"))
      (node (ref "VD309") (pin "1") (pinfunction "K_1") (pintype "passive"))
      (node (ref "VT309") (pin "1") (pinfunction "D_1") (pintype "passive"))
      (node (ref "VT309") (pin "2") (pinfunction "D_2") (pintype "passive"))
      (node (ref "VT309") (pin "5") (pinfunction "D_5") (pintype "passive"))
      (node (ref "VT309") (pin "6") (pinfunction "D_6") (pintype "passive"))
      (node (ref "VT311") (pin "2") (pinfunction "C_2") (pintype "passive"))
      (node (ref "VT311") (pin "4") (pinfunction "C_4") (pintype "passive"))
      (node (ref "VT312") (pin "2") (pinfunction "D_2") (pintype "passive"))
      (node (ref "VT315") (pin "2") (pinfunction "C_2") (pintype "passive"))
    )
    (net (code "30") (name "Net-(VD311-A)") (class "Default")
      (node (ref "C314") (pin "2") (pinfunction "2_2") (pintype "passive"))
      (node (ref "C317") (pin "2") (pinfunction "2_2") (pintype "passive"))
      (node (ref "C318") (pin "1") (pinfunction "1_1") (pintype "passive"))
      (node (ref "VD311") (pin "2") (pinfunction "A_2") (pintype "passive"))
      (node (ref "VD312") (pin "3") (pinfunction "A_3") (pintype "passive"))
      (node (ref "VD313") (pin "1") (pinfunction "K_1") (pintype "passive"))
      (node (ref "VT310") (pin "4") (pinfunction "S_4") (pintype "passive"))
      (node (ref "VT313") (pin "2") (pinfunction "D_2") (pintype "passive"))
      (node (ref "VT314") (pin "2") (pinfunction "C_2") (pintype "passive"))
      (node (ref "VT314") (pin "4") (pinfunction "C_4") (pintype "passive"))
      (node (ref "VT316") (pin "2") (pinfunction "C_2") (pintype "passive"))
    )
    (net (code "31") (name "Net-(VT301-B)") (class "Default")
      (node (ref "C309") (pin "2") (pinfunction "2_2") (pintype "passive"))
      (node (ref "R307") (pin "1") (pinfunction "1_1") (pintype "passive"))
      (node (ref "VT301") (pin "1") (pinfunction "B_1") (pintype "passive"))
      (node (ref "VT301") (pin "2") (pinfunction "C_2") (pintype "passive"))
      (node (ref "VT301") (pin "4") (pinfunction "C_4") (pintype "passive"))
      (node (ref "VT302") (pin "1") (pinfunction "B_1") (pintype "passive"))
    )
    (net (code "32") (name "Net-(VT301-E)") (class "Default")
      (node (ref "R305") (pin "2") (pinfunction "2_2") (pintype "passive"))
      (node (ref "VT301") (pin "3") (pinfunction "E_3") (pintype "passive"))
    )
    (net (code "33") (name "Net-(VT302-E)") (class "Default")
      (node (ref "R306") (pin "2") (pinfunction "2_2") (pintype "passive"))
      (node (ref "VT302") (pin "3") (pinfunction "E_3") (pintype "passive"))
    )
    (net (code "34") (name "Net-(VT303-B)") (class "Default")
      (node (ref "C310") (pin "2") (pinfunction "2_2") (pintype "passive"))
      (node (ref "R308") (pin "1") (pinfunction "1_1") (pintype "passive"))
      (node (ref "VT303") (pin "1") (pinfunction "B_1") (pintype "passive"))
      (node (ref "VT303") (pin "2") (pinfunction "C_2") (pintype "passive"))
      (node (ref "VT303") (pin "4") (pinfunction "C_4") (pintype "passive"))
      (node (ref "VT304") (pin "1") (pinfunction "B_1") (pintype "passive"))
    )
    (net (code "35") (name "Net-(VT303-E)") (class "Default")
      (node (ref "R309") (pin "2") (pinfunction "2_2") (pintype "passive"))
      (node (ref "VT303") (pin "3") (pinfunction "E_3") (pintype "passive"))
    )
    (net (code "36") (name "Net-(VT304-E)") (class "Default")
      (node (ref "R310") (pin "2") (pinfunction "2_2") (pintype "passive"))
      (node (ref "VT304") (pin "3") (pinfunction "E_3") (pintype "passive"))
    )
    (net (code "37") (name "Net-(VT305-B)") (class "Default")
      (node (ref "R311") (pin "2") (pinfunction "2_2") (pintype "passive"))
      (node (ref "R312") (pin "2") (pinfunction "2_2") (pintype "passive"))
      (node (ref "VT305") (pin "1") (pinfunction "B_1") (pintype "passive"))
    )
    (net (code "38") (name "Net-(VT306-B)") (class "Default")
      (node (ref "R318") (pin "2") (pinfunction "2_2") (pintype "passive"))
      (node (ref "R319") (pin "2") (pinfunction "2_2") (pintype "passive"))
      (node (ref "VT306") (pin "1") (pinfunction "B_1") (pintype "passive"))
    )
    (net (code "39") (name "Net-(VT307-B)") (class "Default")
      (node (ref "R323") (pin "1") (pinfunction "1_1") (pintype "passive"))
      (node (ref "VT307") (pin "1") (pinfunction "B_1") (pintype "passive"))
    )
    (net (code "40") (name "Net-(VT308-B)") (class "Default")
      (node (ref "R327") (pin "1") (pinfunction "1_1") (pintype "passive"))
      (node (ref "VT308") (pin "1") (pinfunction "B_1") (pintype "passive"))
    )
    (net (code "41") (name "Net-(VT309-G)") (class "Default")
      (node (ref "R315") (pin "2") (pinfunction "2_2") (pintype "passive"))
      (node (ref "VT307") (pin "2") (pinfunction "C_2") (pintype "passive"))
      (node (ref "VT307") (pin "4") (pinfunction "C_4") (pintype "passive"))
      (node (ref "VT309") (pin "3") (pinfunction "G_3") (pintype "passive"))
    )
    (net (code "42") (name "Net-(VT309-S)") (class "Default")
      (node (ref "R321") (pin "1") (pinfunction "1_1") (pintype "passive"))
      (node (ref "VT309") (pin "4") (pinfunction "S_4") (pintype "passive"))
    )
    (net (code "43") (name "Net-(VT310-G)") (class "Default")
      (node (ref "R316") (pin "2") (pinfunction "2_2") (pintype "passive"))
      (node (ref "VT308") (pin "2") (pinfunction "C_2") (pintype "passive"))
      (node (ref "VT308") (pin "4") (pinfunction "C_4") (pintype "passive"))
      (node (ref "VT310") (pin "3") (pinfunction "G_3") (pintype "passive"))
    )
    (net (code "44") (name "Net-(VT311-B)") (class "Default")
      (node (ref "R314") (pin "2") (pinfunction "2_2") (pintype "passive"))
      (node (ref "R330") (pin "1") (pinfunction "1_1") (pintype "passive"))
      (node (ref "VT311") (pin "1") (pinfunction "B_1") (pintype "passive"))
    )
    (net (code "45") (name "Net-(VT311-E)") (class "Default")
      (node (ref "VT311") (pin "3") (pinfunction "E_3") (pintype "passive"))
      (node (ref "VT315") (pin "1") (pinfunction "B_1") (pintype "passive"))
    )
    (net (code "46") (name "Net-(VT312-G)") (class "Default")
      (node (ref "C313") (pin "2") (pinfunction "2_2") (pintype "passive"))
      (node (ref "R321") (pin "2") (pinfunction "2_2") (pintype "passive"))
      (node (ref "R322") (pin "2") (pinfunction "2_2") (pintype "passive"))
      (node (ref "VT312") (pin "1") (pinfunction "G_1") (pintype "passive"))
    )
    (net (code "47") (name "Net-(VT312-S)") (class "Default")
      (node (ref "R322") (pin "1") (pinfunction "1_1") (pintype "passive"))
      (node (ref "R323") (pin "2") (pinfunction "2_2") (pintype "passive"))
      (node (ref "R324") (pin "2") (pinfunction "2_2") (pintype "passive"))
      (node (ref "VT312") (pin "3") (pinfunction "S_3") (pintype "passive"))
    )
    (net (code "48") (name "Net-(VT313-G)") (class "Default")
      (node (ref "C314") (pin "1") (pinfunction "1_1") (pintype "passive"))
      (node (ref "R328") (pin "1") (pinfunction "1_1") (pintype "passive"))
      (node (ref "R329") (pin "2") (pinfunction "2_2") (pintype "passive"))
      (node (ref "VT313") (pin "1") (pinfunction "G_1") (pintype "passive"))
    )
    (net (code "49") (name "Net-(VT313-S)") (class "Default")
      (node (ref "R326") (pin "1") (pinfunction "1_1") (pintype "passive"))
      (node (ref "R327") (pin "2") (pinfunction "2_2") (pintype "passive"))
      (node (ref "R328") (pin "2") (pinfunction "2_2") (pintype "passive"))
      (node (ref "VT313") (pin "3") (pinfunction "S_3") (pintype "passive"))
    )
    (net (code "50") (name "Net-(VT314-B)") (class "Default")
      (node (ref "R320") (pin "2") (pinfunction "2_2") (pintype "passive"))
      (node (ref "R331") (pin "1") (pinfunction "1_1") (pintype "passive"))
      (node (ref "VT314") (pin "1") (pinfunction "B_1") (pintype "passive"))
    )
    (net (code "51") (name "Net-(VT314-E)") (class "Default")
      (node (ref "VT314") (pin "3") (pinfunction "E_3") (pintype "passive"))
      (node (ref "VT316") (pin "1") (pinfunction "B_1") (pintype "passive"))
    )
    (net (code "52") (name "PR") (class "Default")
      (node (ref "C309") (pin "1") (pinfunction "1_1") (pintype "passive"))
      (node (ref "R315") (pin "1") (pinfunction "1_1") (pintype "passive"))
      (node (ref "VD303") (pin "2") (pinfunction "A_2") (pintype "passive"))
      (node (ref "VT302") (pin "2") (pinfunction "C_2") (pintype "passive"))
      (node (ref "VT302") (pin "4") (pinfunction "C_4") (pintype "passive"))
    )
  )
)
